# modular_pcb1.net
KiCad netlist of a schematic drawn in EAGLE
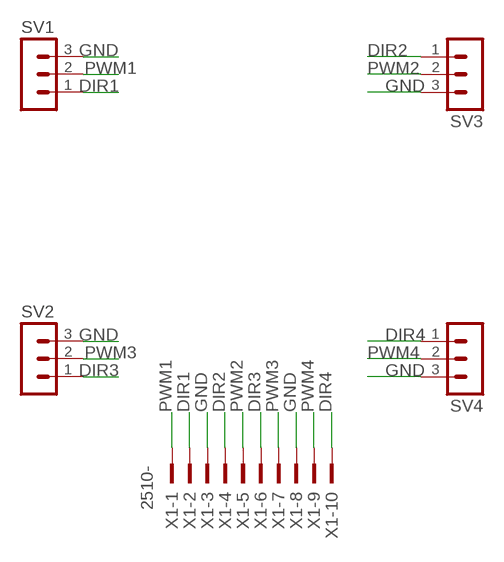
[diagram p0: schematic, sheet 1]

(export (version "E")
  (design (tool "Eeschema 10.0.6"))
  (components
    (comp (ref "SV1")
      (value "MA03-1")
      (footprint "eagle-import:MA03-1")
      (libsource (lib "eagle-import") (part "MA03-1"))
    )
    (comp (ref "SV2")
      (value "MA03-1")
      (footprint "eagle-import:MA03-1")
      (libsource (lib "eagle-import") (part "MA03-1"))
    )
    (comp (ref "SV3")
      (value "MA03-1")
      (footprint "eagle-import:MA03-1")
      (libsource (lib "eagle-import") (part "MA03-1"))
    )
    (comp (ref "SV4")
      (value "MA03-1")
      (footprint "eagle-import:MA03-1")
      (libsource (lib "eagle-import") (part "MA03-1"))
    )
    (comp (ref "X1")
      (value "2510-")
      (footprint "eagle-import:PAK100_2500-10")
      (fields (field (name "MF") "3M") (field (name "MPN") "2510-6002UB"))
      (libsource (lib "eagle-import") (part "2510-"))
    )
  )
  (nets
    (net (code "1") (name "/DIR1") (class "Default")
      (node (ref "SV1") (pin "1") (pinfunction "1_1") (pintype "passive"))
      (node (ref "X1") (pin "2") (pinfunction "KL_2") (pintype "passive"))
    )
    (net (code "2") (name "/DIR2") (class "Default")
      (node (ref "SV3") (pin "1") (pinfunction "1_1") (pintype "passive"))
      (node (ref "X1") (pin "4") (pinfunction "KL_4") (pintype "passive"))
    )
    (net (code "3") (name "/DIR3") (class "Default")
      (node (ref "SV2") (pin "1") (pinfunction "1_1") (pintype "passive"))
      (node (ref "X1") (pin "6") (pinfunction "KL_6") (pintype "passive"))
    )
    (net (code "4") (name "/DIR4") (class "Default")
      (node (ref "SV4") (pin "1") (pinfunction "1_1") (pintype "passive"))
      (node (ref "X1") (pin "10") (pinfunction "KL_10") (pintype "passive"))
    )
    (net (code "5") (name "/GND") (class "Default")
      (node (ref "SV1") (pin "3") (pinfunction "3_3") (pintype "passive"))
      (node (ref "SV2") (pin "3") (pinfunction "3_3") (pintype "passive"))
      (node (ref "SV3") (pin "3") (pinfunction "3_3") (pintype "passive"))
      (node (ref "SV4") (pin "3") (pinfunction "3_3") (pintype "passive"))
      (node (ref "X1") (pin "3") (pinfunction "KL_3") (pintype "passive"))
      (node (ref "X1") (pin "8") (pinfunction "KL_8") (pintype "passive"))
    )
    (net (code "6") (name "/PWM1") (class "Default")
      (node (ref "SV1") (pin "2") (pinfunction "2_2") (pintype "passive"))
      (node (ref "X1") (pin "1") (pinfunction "KL_1") (pintype "passive"))
    )
    (net (code "7") (name "/PWM2") (class "Default")
      (node (ref "SV3") (pin "2") (pinfunction "2_2") (pintype "passive"))
      (node (ref "X1") (pin "5") (pinfunction "KL_5") (pintype "passive"))
    )
    (net (code "8") (name "/PWM3") (class "Default")
      (node (ref "SV2") (pin "2") (pinfunction "2_2") (pintype "passive"))
      (node (ref "X1") (pin "7") (pinfunction "KL_7") (pintype "passive"))
    )
    (net (code "9") (name "/PWM4") (class "Default")
      (node (ref "SV4") (pin "2") (pinfunction "2_2") (pintype "passive"))
      (node (ref "X1") (pin "9") (pinfunction "KL_9") (pintype "passive"))
    )
  )
)
